# ssslidar_v1_0_blade_SIG_bottom.net
KiCad netlist of a schematic drawn in EAGLE
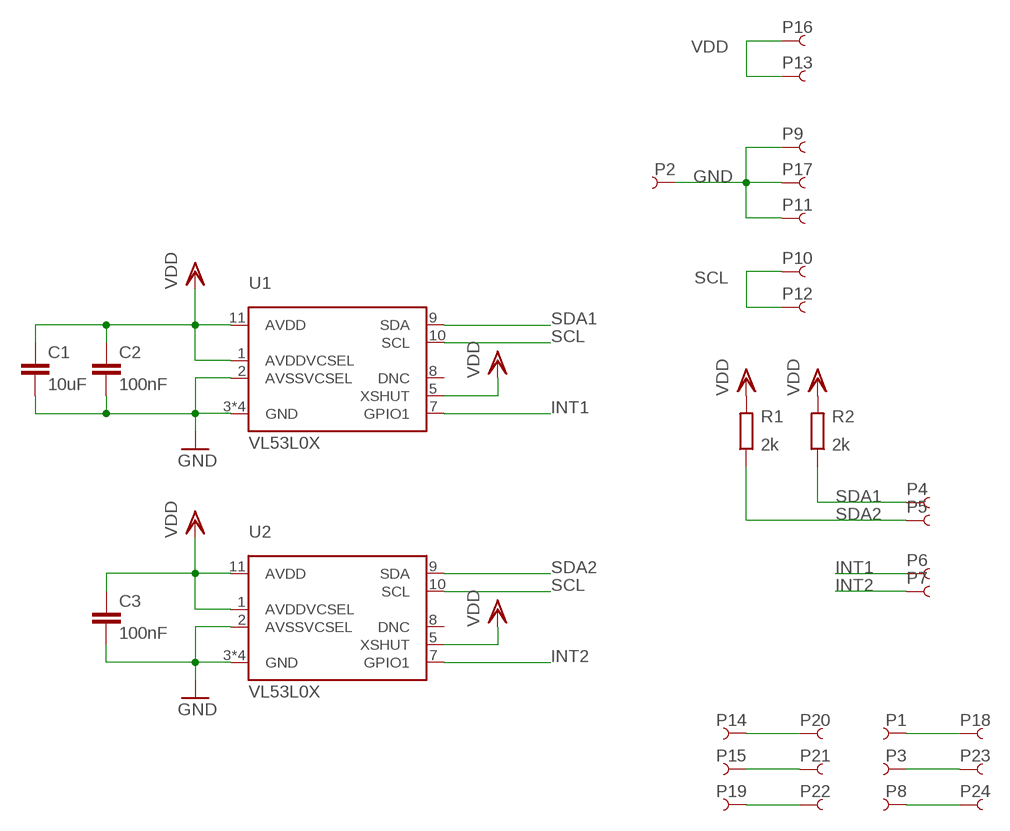
[diagram p0: schematic, sheet 1]

(export (version "E")
  (design (tool "Eeschema 10.0.6"))
  (components
    (comp (ref "C1")
      (value "10uF")
      (footprint "eagle-import:0805_N")
      (libsource (lib "eagle-import") (part "C0805"))
    )
    (comp (ref "C2")
      (value "100nF")
      (footprint "eagle-import:0402_N")
      (libsource (lib "eagle-import") (part "C0402"))
    )
    (comp (ref "C3")
      (value "100nF")
      (footprint "eagle-import:0402_N")
      (libsource (lib "eagle-import") (part "C0402"))
    )
    (comp (ref "P1")
      (value "PIN_SMD_0.8X1_RECT")
      (footprint "eagle-import:PIN_SMD_0.8X1_RECT")
      (libsource (lib "eagle-import") (part "PIN_SMD_0.8X1_RECT"))
    )
    (comp (ref "P2")
      (value "PIN_SMD_1X2")
      (footprint "eagle-import:PIN_SMD_1X2")
      (libsource (lib "eagle-import") (part "PIN_SMD_1X2"))
    )
    (comp (ref "P3")
      (value "PIN_SMD_0.8X1_RECT")
      (footprint "eagle-import:PIN_SMD_0.8X1_RECT")
      (libsource (lib "eagle-import") (part "PIN_SMD_0.8X1_RECT"))
    )
    (comp (ref "P4")
      (value "PIN_SMD_0.8X1_RECT")
      (footprint "eagle-import:PIN_SMD_0.8X1_RECT")
      (libsource (lib "eagle-import") (part "PIN_SMD_0.8X1_RECT"))
    )
    (comp (ref "P5")
      (value "PIN_SMD_0.8X1_RECT")
      (footprint "eagle-import:PIN_SMD_0.8X1_RECT")
      (libsource (lib "eagle-import") (part "PIN_SMD_0.8X1_RECT"))
    )
    (comp (ref "P6")
      (value "PIN_SMD_0.8X1_RECT")
      (footprint "eagle-import:PIN_SMD_0.8X1_RECT")
      (libsource (lib "eagle-import") (part "PIN_SMD_0.8X1_RECT"))
    )
    (comp (ref "P7")
      (value "PIN_SMD_0.8X1_RECT")
      (footprint "eagle-import:PIN_SMD_0.8X1_RECT")
      (libsource (lib "eagle-import") (part "PIN_SMD_0.8X1_RECT"))
    )
    (comp (ref "P8")
      (value "PIN_SMD_0.8X1_RECT")
      (footprint "eagle-import:PIN_SMD_0.8X1_RECT")
      (libsource (lib "eagle-import") (part "PIN_SMD_0.8X1_RECT"))
    )
    (comp (ref "P9")
      (value "PIN_SMD_1X2")
      (footprint "eagle-import:PIN_SMD_1X2")
      (libsource (lib "eagle-import") (part "PIN_SMD_1X2"))
    )
    (comp (ref "P10")
      (value "PIN_SMD_1X2")
      (footprint "eagle-import:PIN_SMD_1X2")
      (libsource (lib "eagle-import") (part "PIN_SMD_1X2"))
    )
    (comp (ref "P11")
      (value "PIN_SMD_1X2")
      (footprint "eagle-import:PIN_SMD_1X2")
      (libsource (lib "eagle-import") (part "PIN_SMD_1X2"))
    )
    (comp (ref "P12")
      (value "PIN_SMD_1X2")
      (footprint "eagle-import:PIN_SMD_1X2")
      (libsource (lib "eagle-import") (part "PIN_SMD_1X2"))
    )
    (comp (ref "P13")
      (value "PIN_SMD_1X2")
      (footprint "eagle-import:PIN_SMD_1X2")
      (libsource (lib "eagle-import") (part "PIN_SMD_1X2"))
    )
    (comp (ref "P14")
      (value "PIN_SMD_0.8X1_RECT")
      (footprint "eagle-import:PIN_SMD_0.8X1_RECT")
      (libsource (lib "eagle-import") (part "PIN_SMD_0.8X1_RECT"))
    )
    (comp (ref "P15")
      (value "PIN_SMD_0.8X1_RECT")
      (footprint "eagle-import:PIN_SMD_0.8X1_RECT")
      (libsource (lib "eagle-import") (part "PIN_SMD_0.8X1_RECT"))
    )
    (comp (ref "P16")
      (value "PIN_SMD_1X2")
      (footprint "eagle-import:PIN_SMD_1X2")
      (libsource (lib "eagle-import") (part "PIN_SMD_1X2"))
    )
    (comp (ref "P17")
      (value "PIN_SMD_1X2")
      (footprint "eagle-import:PIN_SMD_1X2")
      (libsource (lib "eagle-import") (part "PIN_SMD_1X2"))
    )
    (comp (ref "P18")
      (value "PIN_SMD_0.8X1_RECT")
      (footprint "eagle-import:PIN_SMD_0.8X1_RECT")
      (libsource (lib "eagle-import") (part "PIN_SMD_0.8X1_RECT"))
    )
    (comp (ref "P19")
      (value "PIN_SMD_0.8X1_RECT")
      (footprint "eagle-import:PIN_SMD_0.8X1_RECT")
      (libsource (lib "eagle-import") (part "PIN_SMD_0.8X1_RECT"))
    )
    (comp (ref "P20")
      (value "PIN_SMD_0.8X1_RECT")
      (footprint "eagle-import:PIN_SMD_0.8X1_RECT")
      (libsource (lib "eagle-import") (part "PIN_SMD_0.8X1_RECT"))
    )
    (comp (ref "P21")
      (value "PIN_SMD_0.8X1_RECT")
      (footprint "eagle-import:PIN_SMD_0.8X1_RECT")
      (libsource (lib "eagle-import") (part "PIN_SMD_0.8X1_RECT"))
    )
    (comp (ref "P22")
      (value "PIN_SMD_0.8X1_RECT")
      (footprint "eagle-import:PIN_SMD_0.8X1_RECT")
      (libsource (lib "eagle-import") (part "PIN_SMD_0.8X1_RECT"))
    )
    (comp (ref "P23")
      (value "PIN_SMD_0.8X1_RECT")
      (footprint "eagle-import:PIN_SMD_0.8X1_RECT")
      (libsource (lib "eagle-import") (part "PIN_SMD_0.8X1_RECT"))
    )
    (comp (ref "P24")
      (value "PIN_SMD_0.8X1_RECT")
      (footprint "eagle-import:PIN_SMD_0.8X1_RECT")
      (libsource (lib "eagle-import") (part "PIN_SMD_0.8X1_RECT"))
    )
    (comp (ref "R1")
      (value "2k")
      (footprint "eagle-import:0402_N")
      (libsource (lib "eagle-import") (part "R0402"))
    )
    (comp (ref "R2")
      (value "2k")
      (footprint "eagle-import:0402_N")
      (libsource (lib "eagle-import") (part "R0402"))
    )
    (comp (ref "U1")
      (value "VL53L0X")
      (footprint "eagle-import:VL53L0X")
      (libsource (lib "eagle-import") (part "VL53L0X"))
    )
    (comp (ref "U2")
      (value "VL53L0X")
      (footprint "eagle-import:VL53L0X")
      (libsource (lib "eagle-import") (part "VL53L0X"))
    )
  )
  (nets
    (net (code "1") (name "/INT1") (class "Default")
      (node (ref "P6") (pin "PIN") (pinfunction "1_PIN") (pintype "bidirectional"))
      (node (ref "U1") (pin "7") (pinfunction "GPIO1_7") (pintype "bidirectional"))
    )
    (net (code "2") (name "/INT2") (class "Default")
      (node (ref "P7") (pin "PIN") (pinfunction "1_PIN") (pintype "bidirectional"))
      (node (ref "U2") (pin "7") (pinfunction "GPIO1_7") (pintype "bidirectional"))
    )
    (net (code "3") (name "/SCL") (class "Default")
      (node (ref "P10") (pin "P$1") (pinfunction "1_P$1") (pintype "bidirectional"))
      (node (ref "P12") (pin "P$1") (pinfunction "1_P$1") (pintype "bidirectional"))
      (node (ref "U1") (pin "10") (pinfunction "SCL_10") (pintype "bidirectional"))
      (node (ref "U2") (pin "10") (pinfunction "SCL_10") (pintype "bidirectional"))
    )
    (net (code "4") (name "/SDA1") (class "Default")
      (node (ref "P4") (pin "PIN") (pinfunction "1_PIN") (pintype "bidirectional"))
      (node (ref "R2") (pin "1") (pinfunction "1_1") (pintype "passive"))
      (node (ref "U1") (pin "9") (pinfunction "SDA_9") (pintype "bidirectional"))
    )
    (net (code "5") (name "/SDA2") (class "Default")
      (node (ref "P5") (pin "PIN") (pinfunction "1_PIN") (pintype "bidirectional"))
      (node (ref "R1") (pin "1") (pinfunction "1_1") (pintype "passive"))
      (node (ref "U2") (pin "9") (pinfunction "SDA_9") (pintype "bidirectional"))
    )
    (net (code "6") (name "GND") (class "Default")
      (node (ref "C1") (pin "2") (pinfunction "2_2") (pintype "passive"))
      (node (ref "C2") (pin "2") (pinfunction "2_2") (pintype "passive"))
      (node (ref "C3") (pin "2") (pinfunction "2_2") (pintype "passive"))
      (node (ref "P11") (pin "P$1") (pinfunction "1_P$1") (pintype "bidirectional"))
      (node (ref "P17") (pin "P$1") (pinfunction "1_P$1") (pintype "bidirectional"))
      (node (ref "P2") (pin "P$1") (pinfunction "1_P$1") (pintype "bidirectional"))
      (node (ref "P9") (pin "P$1") (pinfunction "1_P$1") (pintype "bidirectional"))
      (node (ref "U1") (pin "12") (pinfunction "GND_12") (pintype "bidirectional"))
      (node (ref "U1") (pin "2") (pinfunction "AVSSVCSEL_2") (pintype "bidirectional"))
      (node (ref "U1") (pin "3") (pinfunction "GND_3") (pintype "bidirectional"))
      (node (ref "U1") (pin "4") (pinfunction "GND_4") (pintype "bidirectional"))
      (node (ref "U1") (pin "6") (pinfunction "GND_6") (pintype "bidirectional"))
      (node (ref "U2") (pin "12") (pinfunction "GND_12") (pintype "bidirectional"))
      (node (ref "U2") (pin "2") (pinfunction "AVSSVCSEL_2") (pintype "bidirectional"))
      (node (ref "U2") (pin "3") (pinfunction "GND_3") (pintype "bidirectional"))
      (node (ref "U2") (pin "4") (pinfunction "GND_4") (pintype "bidirectional"))
      (node (ref "U2") (pin "6") (pinfunction "GND_6") (pintype "bidirectional"))
    )
    (net (code "7") (name "Net-(P1-1)") (class "Default")
      (node (ref "P1") (pin "PIN") (pinfunction "1_PIN") (pintype "bidirectional"))
      (node (ref "P18") (pin "PIN") (pinfunction "1_PIN") (pintype "bidirectional"))
    )
    (net (code "8") (name "Net-(P14-1)") (class "Default")
      (node (ref "P14") (pin "PIN") (pinfunction "1_PIN") (pintype "bidirectional"))
      (node (ref "P20") (pin "PIN") (pinfunction "1_PIN") (pintype "bidirectional"))
    )
    (net (code "9") (name "Net-(P15-1)") (class "Default")
      (node (ref "P15") (pin "PIN") (pinfunction "1_PIN") (pintype "bidirectional"))
      (node (ref "P21") (pin "PIN") (pinfunction "1_PIN") (pintype "bidirectional"))
    )
    (net (code "10") (name "Net-(P19-1)") (class "Default")
      (node (ref "P19") (pin "PIN") (pinfunction "1_PIN") (pintype "bidirectional"))
      (node (ref "P22") (pin "PIN") (pinfunction "1_PIN") (pintype "bidirectional"))
    )
    (net (code "11") (name "Net-(P23-1)") (class "Default")
      (node (ref "P23") (pin "PIN") (pinfunction "1_PIN") (pintype "bidirectional"))
      (node (ref "P3") (pin "PIN") (pinfunction "1_PIN") (pintype "bidirectional"))
    )
    (net (code "12") (name "Net-(P24-1)") (class "Default")
      (node (ref "P24") (pin "PIN") (pinfunction "1_PIN") (pintype "bidirectional"))
      (node (ref "P8") (pin "PIN") (pinfunction "1_PIN") (pintype "bidirectional"))
    )
    (net (code "13") (name "VDD") (class "Default")
      (node (ref "C1") (pin "1") (pinfunction "1_1") (pintype "passive"))
      (node (ref "C2") (pin "1") (pinfunction "1_1") (pintype "passive"))
      (node (ref "C3") (pin "1") (pinfunction "1_1") (pintype "passive"))
      (node (ref "P13") (pin "P$1") (pinfunction "1_P$1") (pintype "bidirectional"))
      (node (ref "P16") (pin "P$1") (pinfunction "1_P$1") (pintype "bidirectional"))
      (node (ref "R1") (pin "2") (pinfunction "2_2") (pintype "passive"))
      (node (ref "R2") (pin "2") (pinfunction "2_2") (pintype "passive"))
      (node (ref "U1") (pin "1") (pinfunction "AVDDVCSEL_1") (pintype "bidirectional"))
      (node (ref "U1") (pin "11") (pinfunction "AVDD_11") (pintype "bidirectional"))
      (node (ref "U1") (pin "5") (pinfunction "XSHUT_5") (pintype "bidirectional"))
      (node (ref "U2") (pin "1") (pinfunction "AVDDVCSEL_1") (pintype "bidirectional"))
      (node (ref "U2") (pin "11") (pinfunction "AVDD_11") (pintype "bidirectional"))
      (node (ref "U2") (pin "5") (pinfunction "XSHUT_5") (pintype "bidirectional"))
    )
    (net (code "14") (name "unconnected-(U1-DNC-Pad8)") (class "Default")
      (node (ref "U1") (pin "8") (pinfunction "DNC_8") (pintype "bidirectional"))
    )
    (net (code "15") (name "unconnected-(U2-DNC-Pad8)") (class "Default")
      (node (ref "U2") (pin "8") (pinfunction "DNC_8") (pintype "bidirectional"))
    )
  )
)
